# temaTSC.net
KiCad netlist of a schematic drawn in EAGLE
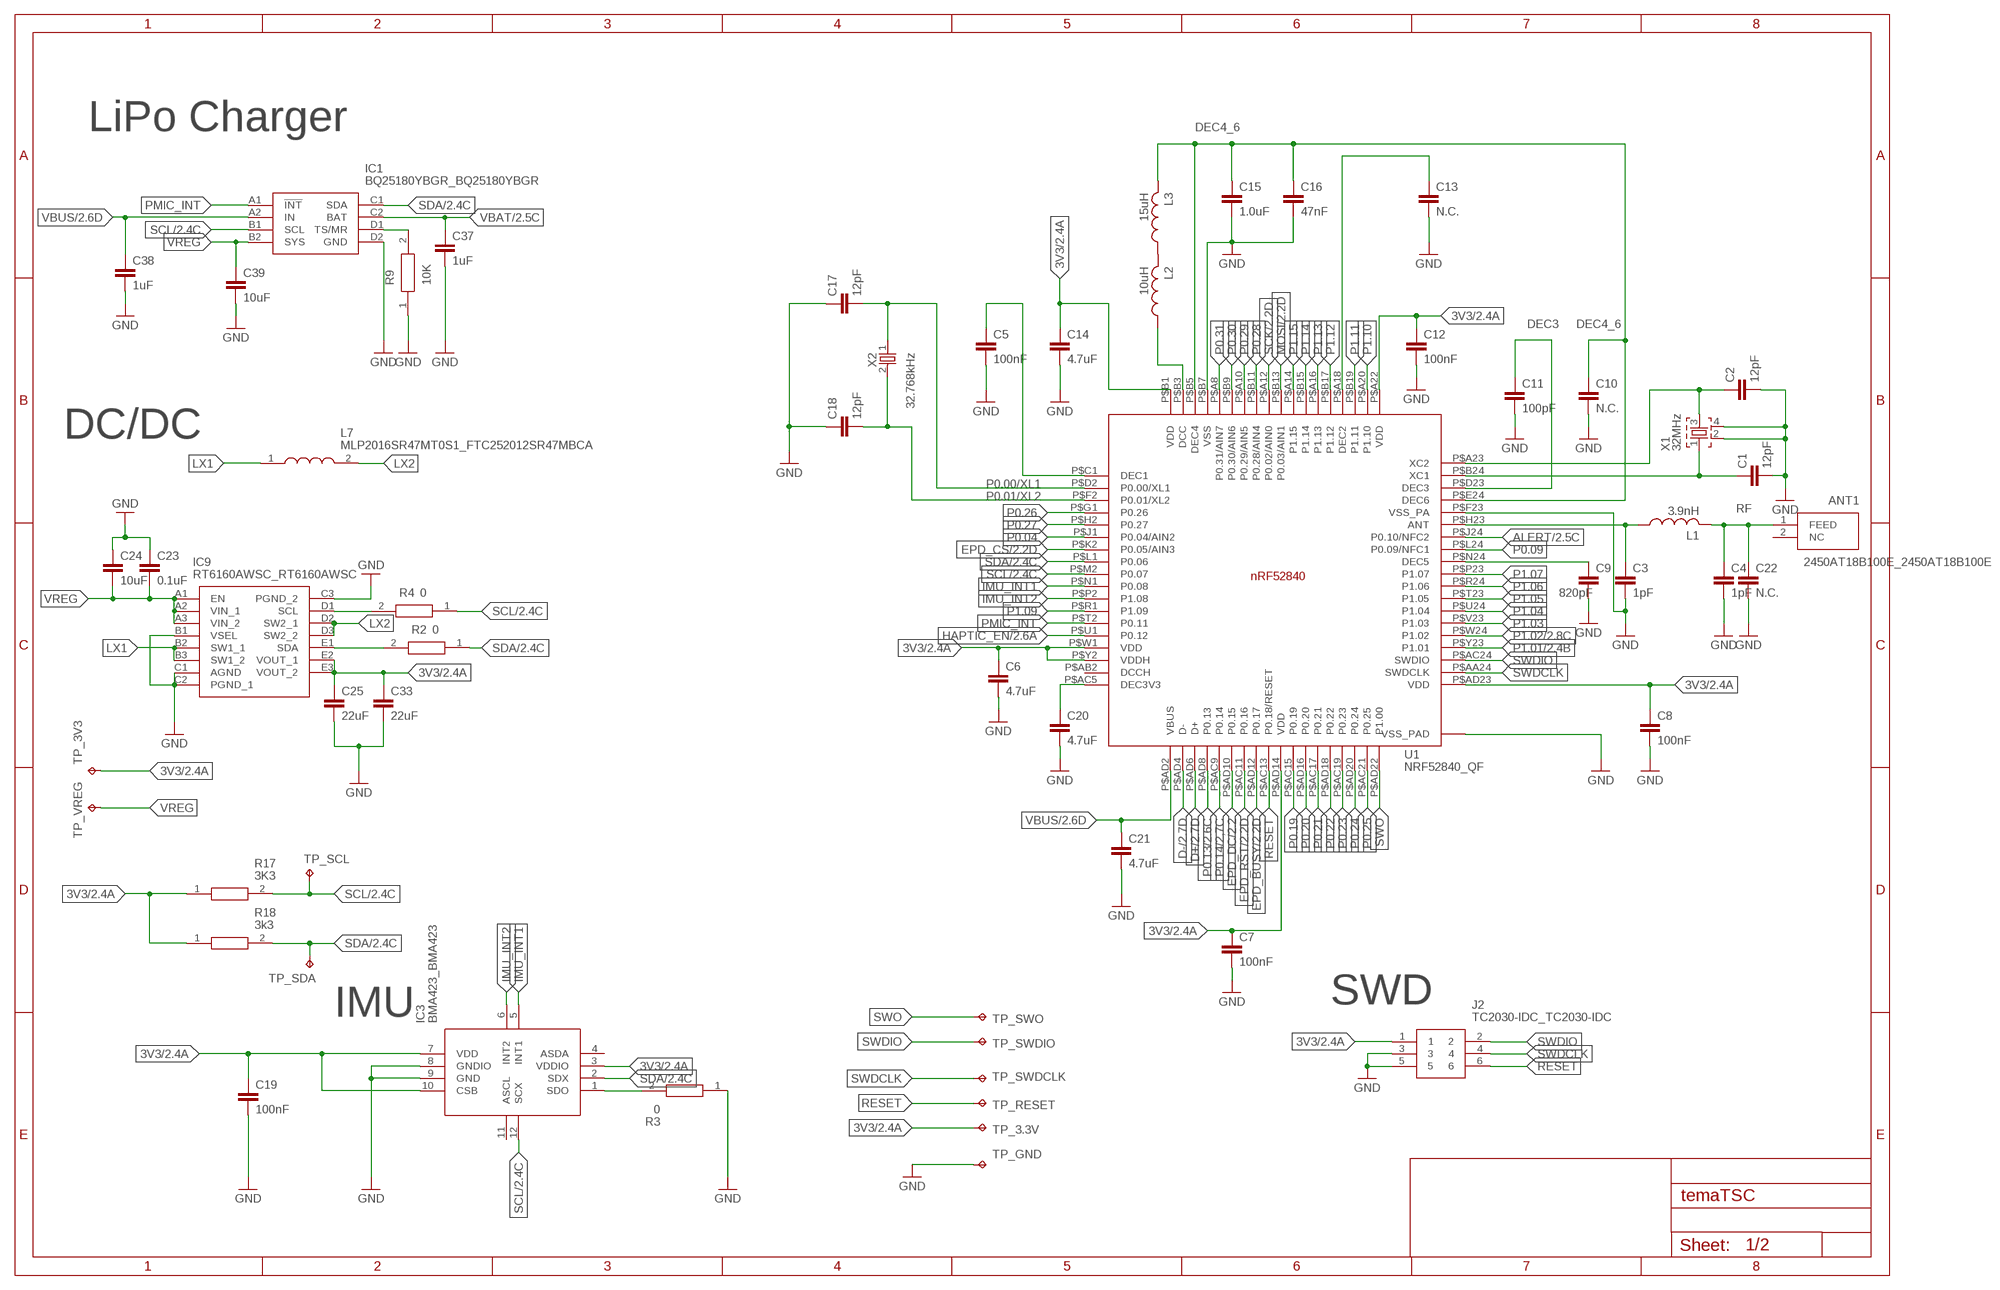
[diagram p0: schematic, sheet 1]
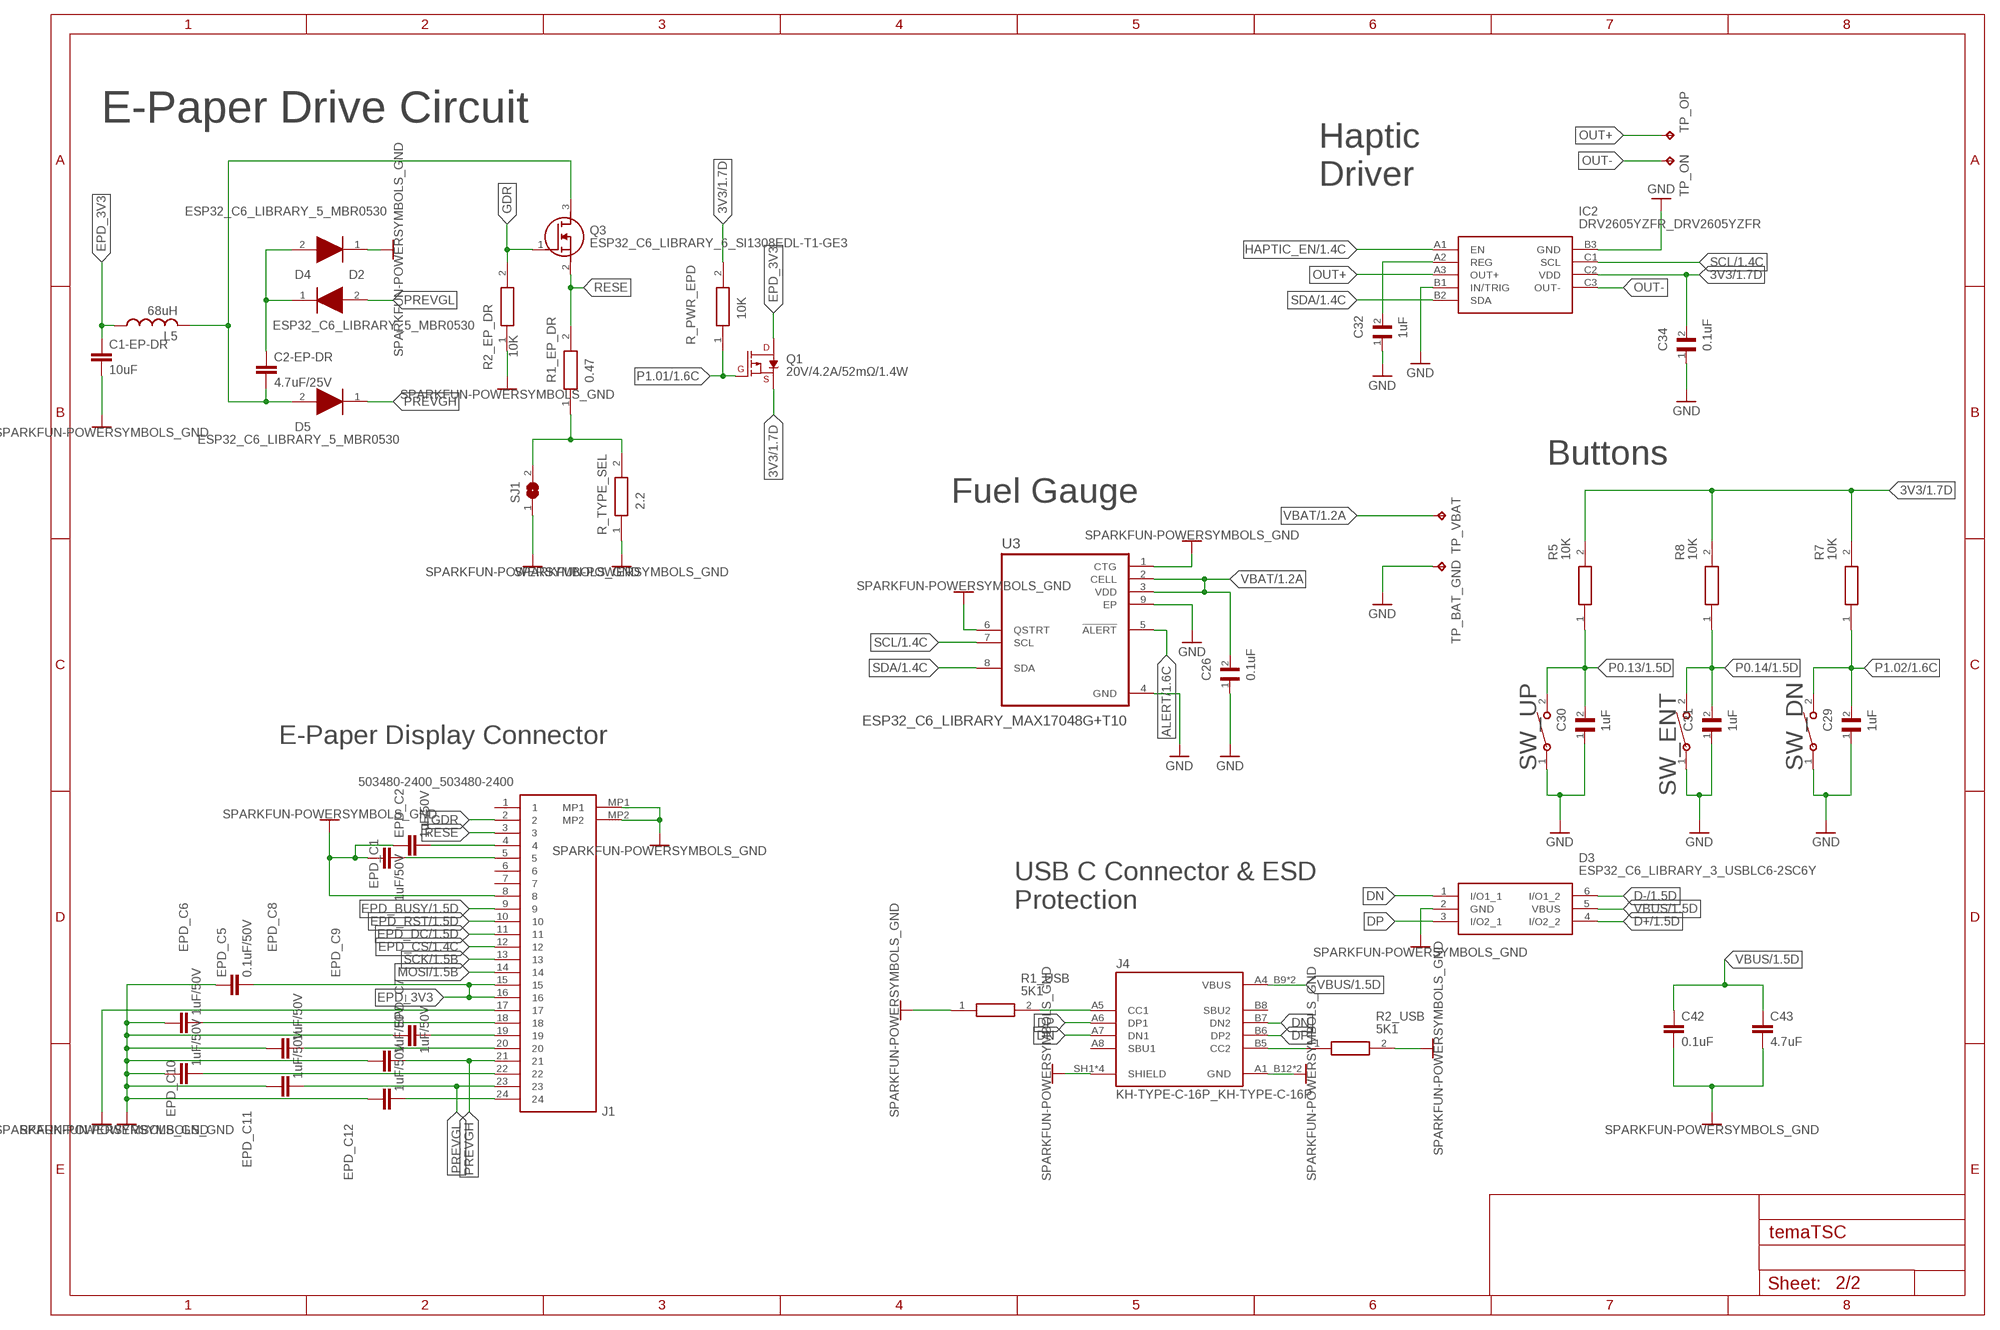
[diagram p1: schematic, sheet 2]

(export (version "E")
  (design (tool "Eeschema 10.0.6"))
  (components
    (comp (ref "ANT1")
      (value "2450AT18B100E_2450AT18B100E")
      (footprint "eagle-import:2450AT18B100E_ANTC3216X140N")
      (fields
        (field (name "ARROW_PART_NUMBER") "2450AT18B100E")
        (field (name "MOUSER_PART_NUMBER") "609-2450AT18B100E")
      )
      (libsource (lib "eagle-import") (part "2450AT18B100E_2450AT18B100E"))
    )
    (comp (ref "C1")
      (value "12pF")
      (footprint "eagle-import:NORDIC_NRF_3_RESC0201_L")
      (libsource (lib "eagle-import") (part "NORDIC_NRF_3_CAPACITOR_0201_L"))
    )
    (comp (ref "C2")
      (value "12pF")
      (footprint "eagle-import:NORDIC_NRF_3_RESC0201_L")
      (libsource (lib "eagle-import") (part "NORDIC_NRF_3_CAPACITOR_0201_L"))
    )
    (comp (ref "C3")
      (value "1pF")
      (footprint "eagle-import:NORDIC_NRF_3_RESC0201_L")
      (libsource (lib "eagle-import") (part "NORDIC_NRF_3_CAPACITOR_0201_L"))
    )
    (comp (ref "C4")
      (value "1pF")
      (footprint "eagle-import:NORDIC_NRF_3_RESC0201_L")
      (libsource (lib "eagle-import") (part "NORDIC_NRF_3_CAPACITOR_0201_L"))
    )
    (comp (ref "C5")
      (value "100nF")
      (footprint "eagle-import:NORDIC_NRF_3_RESC0201_L")
      (libsource (lib "eagle-import") (part "NORDIC_NRF_3_CAPACITOR_0201_L"))
    )
    (comp (ref "C6")
      (value "4.7uF")
      (footprint "eagle-import:NORDIC_NRF_3_RESC0402_L")
      (libsource (lib "eagle-import") (part "NORDIC_NRF_3_CAPACITOR_0402_L"))
    )
    (comp (ref "C7")
      (value "100nF")
      (footprint "eagle-import:NORDIC_NRF_3_RESC0201_L")
      (libsource (lib "eagle-import") (part "NORDIC_NRF_3_CAPACITOR_0201_L"))
    )
    (comp (ref "C8")
      (value "100nF")
      (footprint "eagle-import:NORDIC_NRF_3_RESC0201_L")
      (libsource (lib "eagle-import") (part "NORDIC_NRF_3_CAPACITOR_0201_L"))
    )
    (comp (ref "C9")
      (value "820pF")
      (footprint "eagle-import:NORDIC_NRF_3_RESC0201_L")
      (libsource (lib "eagle-import") (part "NORDIC_NRF_3_CAPACITOR_0201_L"))
    )
    (comp (ref "C10")
      (value "N.C.")
      (footprint "eagle-import:NORDIC_NRF_3_RESC0201_L")
      (libsource (lib "eagle-import") (part "NORDIC_NRF_3_CAPACITOR_0201_L"))
    )
    (comp (ref "C11")
      (value "100pF")
      (footprint "eagle-import:NORDIC_NRF_3_RESC0201_L")
      (libsource (lib "eagle-import") (part "NORDIC_NRF_3_CAPACITOR_0201_L"))
    )
    (comp (ref "C12")
      (value "100nF")
      (footprint "eagle-import:NORDIC_NRF_3_RESC0201_L")
      (libsource (lib "eagle-import") (part "NORDIC_NRF_3_CAPACITOR_0201_L"))
    )
    (comp (ref "C13")
      (value "N.C.")
      (footprint "eagle-import:NORDIC_NRF_3_RESC0201_L")
      (libsource (lib "eagle-import") (part "NORDIC_NRF_3_CAPACITOR_0201_L"))
    )
    (comp (ref "C14")
      (value "4.7uF")
      (footprint "eagle-import:NORDIC_NRF_3_RESC0402_L")
      (libsource (lib "eagle-import") (part "NORDIC_NRF_3_CAPACITOR_0402_L"))
    )
    (comp (ref "C15")
      (value "1.0uF")
      (footprint "eagle-import:NORDIC_NRF_3_RESC0402_L")
      (libsource (lib "eagle-import") (part "NORDIC_NRF_3_CAPACITOR_0402_L"))
    )
    (comp (ref "C16")
      (value "47nF")
      (footprint "eagle-import:NORDIC_NRF_3_RESC0201_L")
      (libsource (lib "eagle-import") (part "NORDIC_NRF_3_CAPACITOR_0201_L"))
    )
    (comp (ref "C17")
      (value "12pF")
      (footprint "eagle-import:NORDIC_NRF_3_RESC0201_L")
      (libsource (lib "eagle-import") (part "NORDIC_NRF_3_CAPACITOR_0201_L"))
    )
    (comp (ref "C18")
      (value "12pF")
      (footprint "eagle-import:NORDIC_NRF_3_RESC0201_L")
      (libsource (lib "eagle-import") (part "NORDIC_NRF_3_CAPACITOR_0201_L"))
    )
    (comp (ref "C19")
      (value "100nF")
      (footprint "eagle-import:NORDIC_NRF_3_RESC0201_L")
      (libsource (lib "eagle-import") (part "NORDIC_NRF_3_CAPACITOR_0201_L"))
    )
    (comp (ref "C20")
      (value "4.7uF")
      (footprint "eagle-import:NORDIC_NRF_3_RESC0402_L")
      (libsource (lib "eagle-import") (part "NORDIC_NRF_3_CAPACITOR_0402_L"))
    )
    (comp (ref "C21")
      (value "4.7uF")
      (footprint "eagle-import:NORDIC_NRF_3_RESC0402_L")
      (libsource (lib "eagle-import") (part "NORDIC_NRF_3_CAPACITOR_0402_L"))
    )
    (comp (ref "C22")
      (value "N.C.")
      (footprint "eagle-import:NORDIC_NRF_3_RESC0201_L")
      (libsource (lib "eagle-import") (part "NORDIC_NRF_3_CAPACITOR_0201_L"))
    )
    (comp (ref "C23")
      (value "0.1uF")
      (footprint "eagle-import:NORDIC_NRF_3_RESC0201_L")
      (libsource (lib "eagle-import") (part "NORDIC_NRF_3_CAPACITOR_0201_L"))
    )
    (comp (ref "C24")
      (value "10uF")
      (footprint "eagle-import:NORDIC_NRF_3_RESC0402_L")
      (libsource (lib "eagle-import") (part "NORDIC_NRF_3_CAPACITOR_0402_L"))
    )
    (comp (ref "C25")
      (value "22uF")
      (footprint "eagle-import:NORDIC_NRF_3_RESC0402_L")
      (libsource (lib "eagle-import") (part "NORDIC_NRF_3_CAPACITOR_0402_L"))
    )
    (comp (ref "C33")
      (value "22uF")
      (footprint "eagle-import:NORDIC_NRF_3_RESC0402_L")
      (libsource (lib "eagle-import") (part "NORDIC_NRF_3_CAPACITOR_0402_L"))
    )
    (comp (ref "C37")
      (value "1uF")
      (footprint "eagle-import:NORDIC_NRF_3_RESC0402_L")
      (libsource (lib "eagle-import") (part "NORDIC_NRF_3_CAPACITOR_0402_L"))
    )
    (comp (ref "C38")
      (value "1uF")
      (footprint "eagle-import:NORDIC_NRF_3_RESC0402_L")
      (libsource (lib "eagle-import") (part "NORDIC_NRF_3_CAPACITOR_0402_L"))
    )
    (comp (ref "C39")
      (value "10uF")
      (footprint "eagle-import:NORDIC_NRF_3_RESC0402_L")
      (libsource (lib "eagle-import") (part "NORDIC_NRF_3_CAPACITOR_0402_L"))
    )
    (comp (ref "IC1")
      (value "BQ25180YBGR_BQ25180YBGR")
      (footprint "eagle-import:BQ25180YBGR_BGA8C40P2X4_100X155X50")
      (fields
        (field (name "ARROW_PART_NUMBER") "BQ25180YBGR")
        (field (name "MOUSER_PART_NUMBER") "595-BQ25180YBGR")
      )
      (libsource (lib "eagle-import") (part "BQ25180YBGR_BQ25180YBGR"))
    )
    (comp (ref "IC3")
      (value "BMA423_BMA423")
      (footprint "eagle-import:BMA423_BMA423")
      (fields (field (name "ARROW_PART_NUMBER") "BMA423") (field (name "MOUSER_PART_NUMBER") "262-BMA423"))
      (libsource (lib "eagle-import") (part "BMA423_BMA423"))
    )
    (comp (ref "IC9")
      (value "RT6160AWSC_RT6160AWSC")
      (footprint "eagle-import:RT6160AWSC_BGA15C40P3X5_140X230X60")
      (fields
        (field (name "MANUFACTURER_PART_NUMBER") "RT6160AWSC")
        (field (name "MOUSER_PART_NUMBER") "835-RT6160AWSC")
      )
      (libsource (lib "eagle-import") (part "RT6160AWSC_RT6160AWSC"))
    )
    (comp (ref "J2")
      (value "TC2030-IDC_TC2030-IDC")
      (footprint "eagle-import:TC2030-IDC_TC2030IDC")
      (fields (field (name "MANUFACTURER_PART_NUMBER") "TC2030-IDC"))
      (libsource (lib "eagle-import") (part "TC2030-IDC_TC2030-IDC"))
    )
    (comp (ref "L1")
      (value "3.9nH")
      (footprint "eagle-import:NORDIC_NRF_2_RESC0402_L")
      (libsource (lib "eagle-import") (part "NORDIC_NRF_2_INDUCTOR_0402_L"))
    )
    (comp (ref "L2")
      (value "10uH")
      (footprint "eagle-import:NORDIC_NRF_2_RESC0402_L")
      (libsource (lib "eagle-import") (part "NORDIC_NRF_2_INDUCTOR_0402_L"))
    )
    (comp (ref "L3")
      (value "15uH")
      (footprint "eagle-import:NORDIC_NRF_2_RESC0402_L")
      (libsource (lib "eagle-import") (part "NORDIC_NRF_2_INDUCTOR_0402_L"))
    )
    (comp (ref "L7")
      (value "MLP2016SR47MT0S1_FTC252012SR47MBCA")
      (footprint "eagle-import:MLP2016SR47MT0S1_INDC2016X100N")
      (fields (field (name "MANUFACTURER_PART_NUMBER") "FTC252012SR47MBCA"))
      (libsource (lib "eagle-import") (part "MLP2016SR47MT0S1_FTC252012SR47MBCA"))
    )
    (comp (ref "R2")
      (value "0")
      (footprint "eagle-import:ERA-1AEB3401C_0201")
      (libsource (lib "eagle-import") (part "ERA-1AEB3401C_CPF0201D7K68C1"))
    )
    (comp (ref "R3")
      (value "0")
      (footprint "eagle-import:ERA-1AEB3401C_0201")
      (libsource (lib "eagle-import") (part "ERA-1AEB3401C_CPF0201D7K68C1"))
    )
    (comp (ref "R4")
      (value "0")
      (footprint "eagle-import:ERA-1AEB3401C_0201")
      (libsource (lib "eagle-import") (part "ERA-1AEB3401C_CPF0201D7K68C1"))
    )
    (comp (ref "R9")
      (value "10K")
      (footprint "eagle-import:ERA-1AEB3401C_0201")
      (libsource (lib "eagle-import") (part "ERA-1AEB3401C_CPF0201D7K68C1"))
    )
    (comp (ref "R17")
      (value "3K3")
      (footprint "eagle-import:ERA-1AEB3401C_0201")
      (libsource (lib "eagle-import") (part "ERA-1AEB3401C_CPF0201D7K68C1"))
    )
    (comp (ref "R18")
      (value "3k3")
      (footprint "eagle-import:ERA-1AEB3401C_0201")
      (libsource (lib "eagle-import") (part "ERA-1AEB3401C_CPF0201D7K68C1"))
    )
    (comp (ref "TP_3.3V")
      (value "HECTOR_WATCH_1_TPTP20R")
      (footprint "eagle-import:HECTOR_WATCH_1_TP20R")
      (libsource (lib "eagle-import") (part "HECTOR_WATCH_1_TPTP20R"))
    )
    (comp (ref "TP_3V3")
      (value "HECTOR_WATCH_1_TPTP20R")
      (footprint "eagle-import:HECTOR_WATCH_1_TP20R")
      (libsource (lib "eagle-import") (part "HECTOR_WATCH_1_TPTP20R"))
    )
    (comp (ref "TP_GND")
      (value "HECTOR_WATCH_1_TPTP20R")
      (footprint "eagle-import:HECTOR_WATCH_1_TP20R")
      (libsource (lib "eagle-import") (part "HECTOR_WATCH_1_TPTP20R"))
    )
    (comp (ref "TP_RESET")
      (value "HECTOR_WATCH_1_TPTP20R")
      (footprint "eagle-import:HECTOR_WATCH_1_TP20R")
      (libsource (lib "eagle-import") (part "HECTOR_WATCH_1_TPTP20R"))
    )
    (comp (ref "TP_SCL")
      (value "HECTOR_WATCH_1_TPTP20R")
      (footprint "eagle-import:HECTOR_WATCH_1_TP20R")
      (libsource (lib "eagle-import") (part "HECTOR_WATCH_1_TPTP20R"))
    )
    (comp (ref "TP_SDA")
      (value "HECTOR_WATCH_1_TPTP20R")
      (footprint "eagle-import:HECTOR_WATCH_1_TP20R")
      (libsource (lib "eagle-import") (part "HECTOR_WATCH_1_TPTP20R"))
    )
    (comp (ref "TP_SWDCLK")
      (value "HECTOR_WATCH_1_TPTP20R")
      (footprint "eagle-import:HECTOR_WATCH_1_TP20R")
      (libsource (lib "eagle-import") (part "HECTOR_WATCH_1_TPTP20R"))
    )
    (comp (ref "TP_SWDIO")
      (value "HECTOR_WATCH_1_TPTP20R")
      (footprint "eagle-import:HECTOR_WATCH_1_TP20R")
      (libsource (lib "eagle-import") (part "HECTOR_WATCH_1_TPTP20R"))
    )
    (comp (ref "TP_SWO")
      (value "HECTOR_WATCH_1_TPTP20R")
      (footprint "eagle-import:HECTOR_WATCH_1_TP20R")
      (libsource (lib "eagle-import") (part "HECTOR_WATCH_1_TPTP20R"))
    )
    (comp (ref "TP_VREG")
      (value "HECTOR_WATCH_1_TPTP20R")
      (footprint "eagle-import:HECTOR_WATCH_1_TP20R")
      (libsource (lib "eagle-import") (part "HECTOR_WATCH_1_TPTP20R"))
    )
    (comp (ref "U1")
      (value "NRF52840_QF")
      (footprint "eagle-import:NORDIC_NRF_4_AQFN50P700X700X85_HS-74N")
      (libsource (lib "eagle-import") (part "NORDIC_NRF_4_NRF52840_QF"))
    )
    (comp (ref "X1")
      (value "32MHz")
      (footprint "eagle-import:NORDIC_NRF_BT-XTAL_2016_N")
      (libsource (lib "eagle-import") (part "NORDIC_NRF_XTAL_32MHZ"))
    )
    (comp (ref "X2")
      (value "32.768kHz")
      (footprint "eagle-import:NORDIC_NRF_1_XTAL_3215_N")
      (libsource (lib "eagle-import") (part "NORDIC_NRF_1_XTAL_32KHZ"))
    )
    (comp (ref "C1-EP-DR")
      (value "10uF")
      (footprint "eagle-import:NORDIC_NRF_3_RESC0402_L")
      (libsource (lib "eagle-import") (part "NORDIC_NRF_3_CAPACITOR_0402_L"))
    )
    (comp (ref "C2-EP-DR")
      (value "4.7uF/25V")
      (footprint "eagle-import:NORDIC_NRF_3_RESC0402_L")
      (libsource (lib "eagle-import") (part "NORDIC_NRF_3_CAPACITOR_0402_L"))
    )
    (comp (ref "C26")
      (value "0.1uF")
      (footprint "eagle-import:GRM011R60J152KE01L_1_0201")
      (libsource (lib "eagle-import") (part "GRM011R60J152KE01L_1_GRM011R60J152KE01L"))
    )
    (comp (ref "C29")
      (value "1uF")
      (footprint "eagle-import:GRM011R60J152KE01L_1_0201")
      (libsource (lib "eagle-import") (part "GRM011R60J152KE01L_1_GRM011R60J152KE01L"))
    )
    (comp (ref "C30")
      (value "1uF")
      (footprint "eagle-import:GRM011R60J152KE01L_1_0201")
      (libsource (lib "eagle-import") (part "GRM011R60J152KE01L_1_GRM011R60J152KE01L"))
    )
    (comp (ref "C31")
      (value "1uF")
      (footprint "eagle-import:GRM011R60J152KE01L_1_0201")
      (libsource (lib "eagle-import") (part "GRM011R60J152KE01L_1_GRM011R60J152KE01L"))
    )
    (comp (ref "C32")
      (value "1uF")
      (footprint "eagle-import:GRM011R60J152KE01L_1_0201")
      (libsource (lib "eagle-import") (part "GRM011R60J152KE01L_1_GRM011R60J152KE01L"))
    )
    (comp (ref "C34")
      (value "0.1uF")
      (footprint "eagle-import:GRM011R60J152KE01L_1_0201")
      (libsource (lib "eagle-import") (part "GRM011R60J152KE01L_1_GRM011R60J152KE01L"))
    )
    (comp (ref "C42")
      (value "0.1uF")
      (footprint "eagle-import:NORDIC_NRF_3_RESC0201_L")
      (libsource (lib "eagle-import") (part "NORDIC_NRF_3_CAPACITOR_0201_L"))
    )
    (comp (ref "C43")
      (value "4.7uF")
      (footprint "eagle-import:NORDIC_NRF_3_RESC0402_L")
      (libsource (lib "eagle-import") (part "NORDIC_NRF_3_CAPACITOR_0402_L"))
    )
    (comp (ref "D2")
      (value "ESP32_C6_LIBRARY_5_MBR0530")
      (footprint "eagle-import:ESP32_C6_LIBRARY_5_SOD3716X135N")
      (fields (field (name "MF") "ON Semiconductor") (field (name "MP") "MBR0530"))
      (libsource (lib "eagle-import") (part "ESP32_C6_LIBRARY_5_MBR0530"))
    )
    (comp (ref "D3")
      (value "ESP32_C6_LIBRARY_3_USBLC6-2SC6Y")
      (footprint "eagle-import:ESP32_C6_LIBRARY_3_SOT95P280X145-6N")
      (fields (field (name "MF") "STMicroelectronics") (field (name "MP") "USBLC6-2SC6Y"))
      (libsource (lib "eagle-import") (part "ESP32_C6_LIBRARY_3_USBLC6-2SC6Y"))
    )
    (comp (ref "D4")
      (value "ESP32_C6_LIBRARY_5_MBR0530")
      (footprint "eagle-import:ESP32_C6_LIBRARY_5_SOD3716X135N")
      (fields (field (name "MF") "ON Semiconductor") (field (name "MP") "MBR0530"))
      (libsource (lib "eagle-import") (part "ESP32_C6_LIBRARY_5_MBR0530"))
    )
    (comp (ref "D5")
      (value "ESP32_C6_LIBRARY_5_MBR0530")
      (footprint "eagle-import:ESP32_C6_LIBRARY_5_SOD3716X135N")
      (fields (field (name "MF") "ON Semiconductor") (field (name "MP") "MBR0530"))
      (libsource (lib "eagle-import") (part "ESP32_C6_LIBRARY_5_MBR0530"))
    )
    (comp (ref "EPD_C1")
      (value "1uF/50V")
      (footprint "eagle-import:NORDIC_NRF_3_RESC0402_L")
      (libsource (lib "eagle-import") (part "NORDIC_NRF_3_CAPACITOR_0402_L"))
    )
    (comp (ref "EPD_C2")
      (value "1uF/50V")
      (footprint "eagle-import:NORDIC_NRF_3_RESC0402_L")
      (libsource (lib "eagle-import") (part "NORDIC_NRF_3_CAPACITOR_0402_L"))
    )
    (comp (ref "EPD_C5")
      (value "0.1uF/50V")
      (footprint "eagle-import:NORDIC_NRF_3_RESC0201_L")
      (libsource (lib "eagle-import") (part "NORDIC_NRF_3_CAPACITOR_0201_L"))
    )
    (comp (ref "EPD_C6")
      (value "1uF/50V")
      (footprint "eagle-import:NORDIC_NRF_3_RESC0402_L")
      (libsource (lib "eagle-import") (part "NORDIC_NRF_3_CAPACITOR_0402_L"))
    )
    (comp (ref "EPD_C7")
      (value "1uF/50V")
      (footprint "eagle-import:NORDIC_NRF_3_RESC0402_L")
      (libsource (lib "eagle-import") (part "NORDIC_NRF_3_CAPACITOR_0402_L"))
    )
    (comp (ref "EPD_C8")
      (value "1uF/50V")
      (footprint "eagle-import:NORDIC_NRF_3_RESC0402_L")
      (libsource (lib "eagle-import") (part "NORDIC_NRF_3_CAPACITOR_0402_L"))
    )
    (comp (ref "EPD_C9")
      (value "1uF/50V")
      (footprint "eagle-import:NORDIC_NRF_3_RESC0402_L")
      (libsource (lib "eagle-import") (part "NORDIC_NRF_3_CAPACITOR_0402_L"))
    )
    (comp (ref "EPD_C10")
      (value "1uF/50V")
      (footprint "eagle-import:NORDIC_NRF_3_RESC0402_L")
      (libsource (lib "eagle-import") (part "NORDIC_NRF_3_CAPACITOR_0402_L"))
    )
    (comp (ref "EPD_C11")
      (value "1uF/50V")
      (footprint "eagle-import:NORDIC_NRF_3_RESC0402_L")
      (libsource (lib "eagle-import") (part "NORDIC_NRF_3_CAPACITOR_0402_L"))
    )
    (comp (ref "EPD_C12")
      (value "1uF/50V")
      (footprint "eagle-import:NORDIC_NRF_3_RESC0402_L")
      (libsource (lib "eagle-import") (part "NORDIC_NRF_3_CAPACITOR_0402_L"))
    )
    (comp (ref "IC2")
      (value "DRV2605YZFR_DRV2605YZFR")
      (footprint "eagle-import:DRV2605YZFR_BGA9C50P3X3_144X144X62")
      (fields (field (name "ARROW_PART_NUMBER") "DRV2605YZFR"))
      (libsource (lib "eagle-import") (part "DRV2605YZFR_DRV2605YZFR"))
    )
    (comp (ref "J1")
      (value "503480-2400_503480-2400")
      (footprint "eagle-import:503480-2400_5034802400")
      (fields
        (field (name "MANUFACTURER_PART_NUMBER") "503480-2400")
        (field (name "MOUSER_PART_NUMBER") "538-503480-2400")
      )
      (libsource (lib "eagle-import") (part "503480-2400_503480-2400"))
    )
    (comp (ref "J4")
      (value "KH-TYPE-C-16P_KH-TYPE-C-16P")
      (footprint "eagle-import:KH-TYPE-C-16P_KINGHELM_KH-TYPE-C-16P")
      (fields (field (name "MF") "kinghelm") (field (name "MP") "KH-TYPE-C-16P"))
      (libsource (lib "eagle-import") (part "KH-TYPE-C-16P_KH-TYPE-C-16P"))
    )
    (comp (ref "L5")
      (value "68uH")
      (footprint "eagle-import:NORDIC_NRF_2_RESC0402_L")
      (libsource (lib "eagle-import") (part "NORDIC_NRF_2_INDUCTOR_0402_L"))
    )
    (comp (ref "Q1")
      (value "20V/4.2A/52mΩ/1.4W")
      (footprint "eagle-import:ESP32_C6_LIBRARY_4_ESP32_C6_LIBRARY_4_ESP32_C6_LIBRARY_4_ESP32_C6_LIBRARY_4_ESP32_WROVER_SPARKFUN-DISCRETESEMI_SOT23-3")
      (libsource (lib "eagle-import") (part "ESP32_C6_LIBRARY_4_ESP32_WROVER_SPARKFUN-DISCRETESEMI_MOSFET_PCH-DMG2305UX-7"))
    )
    (comp (ref "Q3")
      (value "ESP32_C6_LIBRARY_6_SI1308EDL-T1-GE3")
      (footprint "eagle-import:ESP32_C6_LIBRARY_6_SOT65P210X110-3N")
      (fields (field (name "MF") "Vishay Siliconix") (field (name "MP") "SI1308EDL-T1-GE3"))
      (libsource (lib "eagle-import") (part "ESP32_C6_LIBRARY_6_SI1308EDL-T1-GE3"))
    )
    (comp (ref "R1_EP_DR")
      (value "0.47")
      (footprint "eagle-import:ERA-1AEB3401C_0201")
      (libsource (lib "eagle-import") (part "ERA-1AEB3401C_CPF0201D7K68C1"))
    )
    (comp (ref "R1_USB")
      (value "5K1")
      (footprint "eagle-import:ERA-1AEB3401C_0201")
      (libsource (lib "eagle-import") (part "ERA-1AEB3401C_CPF0201D7K68C1"))
    )
    (comp (ref "R2_EP_DR")
      (value "10K")
      (footprint "eagle-import:ERA-1AEB3401C_0201")
      (libsource (lib "eagle-import") (part "ERA-1AEB3401C_CPF0201D7K68C1"))
    )
    (comp (ref "R2_USB")
      (value "5K1")
      (footprint "eagle-import:ERA-1AEB3401C_0201")
      (libsource (lib "eagle-import") (part "ERA-1AEB3401C_CPF0201D7K68C1"))
    )
    (comp (ref "R5")
      (value "10K")
      (footprint "eagle-import:ERA-1AEB3401C_0201")
      (libsource (lib "eagle-import") (part "ERA-1AEB3401C_CPF0201D7K68C1"))
    )
    (comp (ref "R7")
      (value "10K")
      (footprint "eagle-import:ERA-1AEB3401C_0201")
      (libsource (lib "eagle-import") (part "ERA-1AEB3401C_CPF0201D7K68C1"))
    )
    (comp (ref "R8")
      (value "10K")
      (footprint "eagle-import:ERA-1AEB3401C_0201")
      (libsource (lib "eagle-import") (part "ERA-1AEB3401C_CPF0201D7K68C1"))
    )
    (comp (ref "R_PWR_EPD")
      (value "10K")
      (footprint "eagle-import:ERA-1AEB3401C_0201")
      (libsource (lib "eagle-import") (part "ERA-1AEB3401C_CPF0201D7K68C1"))
    )
    (comp (ref "R_TYPE_SEL")
      (value "2.2")
      (footprint "eagle-import:ERA-1AEB3401C_0201")
      (libsource (lib "eagle-import") (part "ERA-1AEB3401C_CPF0201D7K68C1"))
    )
    (comp (ref "SJ1")
      (value "ESP32_C6_LIBRARY_7_JUMPER_SJ")
      (footprint "eagle-import:ESP32_C6_LIBRARY_7_JUMPER_SJ")
      (libsource (lib "eagle-import") (part "ESP32_C6_LIBRARY_7_JUMPER_SJ"))
    )
    (comp (ref "SW_DN")
      (value "2025-10-22_07-23-44_LIBRARY_EVP-AKE31ASW_EVP-AKE31A_PAN")
      (footprint "eagle-import:2025-10-22_07-23-44_LIBRARY_SW_EVP-AKE31A_PAN")
      (fields
        (field (name "MANUFACTURER_PART_NUMBER") "EVP-AKE31A")
        (field (name "COPYRIGHT") "Copyright (C) 2025 Ultra Librarian. All rights reserved.")
      )
      (libsource (lib "eagle-import") (part "2025-10-22_07-23-44_LIBRARY_EVP-AKE31ASW_EVP-AKE31A_PAN"))
    )
    (comp (ref "SW_ENT")
      (value "2025-10-22_07-23-44_LIBRARY_EVP-AKE31ASW_EVP-AKE31A_PAN")
      (footprint "eagle-import:2025-10-22_07-23-44_LIBRARY_SW_EVP-AKE31A_PAN")
      (fields
        (field (name "MANUFACTURER_PART_NUMBER") "EVP-AKE31A")
        (field (name "COPYRIGHT") "Copyright (C) 2025 Ultra Librarian. All rights reserved.")
      )
      (libsource (lib "eagle-import") (part "2025-10-22_07-23-44_LIBRARY_EVP-AKE31ASW_EVP-AKE31A_PAN"))
    )
    (comp (ref "SW_UP")
      (value "2025-10-22_07-23-44_LIBRARY_EVP-AKE31ASW_EVP-AKE31A_PAN")
      (footprint "eagle-import:2025-10-22_07-23-44_LIBRARY_SW_EVP-AKE31A_PAN")
      (fields
        (field (name "MANUFACTURER_PART_NUMBER") "EVP-AKE31A")
        (field (name "COPYRIGHT") "Copyright (C) 2025 Ultra Librarian. All rights reserved.")
      )
      (libsource (lib "eagle-import") (part "2025-10-22_07-23-44_LIBRARY_EVP-AKE31ASW_EVP-AKE31A_PAN"))
    )
    (comp (ref "TP_BAT_GND")
      (value "HECTOR_WATCH_1_TPTP20R")
      (footprint "eagle-import:HECTOR_WATCH_1_TP20R")
      (libsource (lib "eagle-import") (part "HECTOR_WATCH_1_TPTP20R"))
    )
    (comp (ref "TP_ON")
      (value "HECTOR_WATCH_1_TPTP20R")
      (footprint "eagle-import:HECTOR_WATCH_1_TP20R")
      (libsource (lib "eagle-import") (part "HECTOR_WATCH_1_TPTP20R"))
    )
    (comp (ref "TP_OP")
      (value "HECTOR_WATCH_1_TPTP20R")
      (footprint "eagle-import:HECTOR_WATCH_1_TP20R")
      (libsource (lib "eagle-import") (part "HECTOR_WATCH_1_TPTP20R"))
    )
    (comp (ref "TP_VBAT")
      (value "HECTOR_WATCH_1_TPTP20R")
      (footprint "eagle-import:HECTOR_WATCH_1_TP20R")
      (libsource (lib "eagle-import") (part "HECTOR_WATCH_1_TPTP20R"))
    )
    (comp (ref "U3")
      (value "ESP32_C6_LIBRARY_MAX17048G+T10")
      (footprint "eagle-import:ESP32_C6_LIBRARY_SON50P200X200X80-9N")
      (fields (field (name "MF") "Analog Devices") (field (name "MP") "MAX17048G+T10"))
      (libsource (lib "eagle-import") (part "ESP32_C6_LIBRARY_MAX17048G+T10"))
    )
  )
  (nets
    (net (code "1") (name "3V3{slash}1.7D") (class "Default")
      (node (ref "C34") (pin "2") (pinfunction "2_2") (pintype "passive"))
      (node (ref "IC2") (pin "C2") (pinfunction "VDD_C2") (pintype "bidirectional"))
      (node (ref "Q1") (pin "2") (pinfunction "S_2") (pintype "bidirectional"))
      (node (ref "R5") (pin "2") (pinfunction "2_2") (pintype "bidirectional"))
      (node (ref "R7") (pin "2") (pinfunction "2_2") (pintype "bidirectional"))
      (node (ref "R8") (pin "2") (pinfunction "2_2") (pintype "bidirectional"))
      (node (ref "R_PWR_EPD") (pin "2") (pinfunction "2_2") (pintype "bidirectional"))
    )
    (net (code "2") (name "3V3{slash}2.4A") (class "Default")
      (node (ref "C12") (pin "1") (pinfunction "1_1") (pintype "passive"))
      (node (ref "C14") (pin "1") (pinfunction "1_1") (pintype "passive"))
      (node (ref "C19") (pin "1") (pinfunction "1_1") (pintype "passive"))
      (node (ref "C25") (pin "1") (pinfunction "1_1") (pintype "passive"))
      (node (ref "C33") (pin "1") (pinfunction "1_1") (pintype "passive"))
      (node (ref "C6") (pin "1") (pinfunction "1_1") (pintype "passive"))
      (node (ref "C7") (pin "1") (pinfunction "1_1") (pintype "passive"))
      (node (ref "C8") (pin "1") (pinfunction "1_1") (pintype "passive"))
      (node (ref "IC3") (pin "10") (pinfunction "CSB_10") (pintype "bidirectional"))
      (node (ref "IC3") (pin "3") (pinfunction "VDDIO_3") (pintype "bidirectional"))
      (node (ref "IC3") (pin "7") (pinfunction "VDD_7") (pintype "bidirectional"))
      (node (ref "IC9") (pin "E2") (pinfunction "VOUT_1_E2") (pintype "bidirectional"))
      (node (ref "IC9") (pin "E3") (pinfunction "VOUT_2_E3") (pintype "bidirectional"))
      (node (ref "J2") (pin "1") (pinfunction "1_1") (pintype "bidirectional"))
      (node (ref "R17") (pin "1") (pinfunction "1_1") (pintype "bidirectional"))
      (node (ref "R18") (pin "1") (pinfunction "1_1") (pintype "bidirectional"))
      (node (ref "TP_3.3V") (pin "TP") (pinfunction "TP_TP") (pintype "input"))
      (node (ref "TP_3V3") (pin "TP") (pinfunction "TP_TP") (pintype "input"))
      (node (ref "U1") (pin "P$A22") (pinfunction "VDD_P$A22") (pintype "power_in"))
      (node (ref "U1") (pin "P$AD14") (pinfunction "VDD_P$AD14") (pintype "power_in"))
      (node (ref "U1") (pin "P$AD23") (pinfunction "VDD_P$AD23") (pintype "power_in"))
      (node (ref "U1") (pin "P$B1") (pinfunction "VDD_P$B1") (pintype "power_in"))
      (node (ref "U1") (pin "P$W1") (pinfunction "VDD_P$W1") (pintype "power_in"))
      (node (ref "U1") (pin "P$Y2") (pinfunction "VDDH_P$Y2") (pintype "power_in"))
    )
    (net (code "3") (name "ALERT{slash}1.6C") (class "Default")
      (node (ref "U3") (pin "5") (pinfunction "~{ALERT}_5") (pintype "output"))
    )
    (net (code "4") (name "ALERT{slash}2.5C") (class "Default")
      (node (ref "U1") (pin "P$J24") (pinfunction "P0.10/NFC2_P$J24") (pintype "bidirectional"))
    )
    (net (code "5") (name "D+{slash}1.5D") (class "Default")
      (node (ref "D3") (pin "4") (pinfunction "I/O2_2_4") (pintype "bidirectional"))
    )
    (net (code "6") (name "D+{slash}2.7D") (class "Default")
      (node (ref "U1") (pin "P$AD6") (pinfunction "D+_P$AD6") (pintype "bidirectional"))
    )
    (net (code "7") (name "D-{slash}1.5D") (class "Default")
      (node (ref "D3") (pin "6") (pinfunction "I/O1_2_6") (pintype "bidirectional"))
    )
    (net (code "8") (name "D-{slash}2.7D") (class "Default")
      (node (ref "U1") (pin "P$AD4") (pinfunction "D-_P$AD4") (pintype "bidirectional"))
    )
    (net (code "9") (name "DEC3") (class "Default")
      (node (ref "C11") (pin "1") (pinfunction "1_1") (pintype "passive"))
      (node (ref "U1") (pin "P$D23") (pinfunction "DEC3_P$D23") (pintype "bidirectional"))
    )
    (net (code "10") (name "DEC4_6") (class "Default")
      (node (ref "C10") (pin "1") (pinfunction "1_1") (pintype "passive"))
      (node (ref "C15") (pin "1") (pinfunction "1_1") (pintype "passive"))
      (node (ref "C16") (pin "1") (pinfunction "1_1") (pintype "passive"))
      (node (ref "L3") (pin "2") (pinfunction "2_2") (pintype "passive"))
      (node (ref "U1") (pin "P$B5") (pinfunction "DEC4_P$B5") (pintype "power_in"))
      (node (ref "U1") (pin "P$E24") (pinfunction "DEC6_P$E24") (pintype "bidirectional"))
    )
    (net (code "11") (name "DN") (class "Default")
      (node (ref "D3") (pin "1") (pinfunction "I/O1_1_1") (pintype "bidirectional"))
      (node (ref "J4") (pin "A7") (pinfunction "DN1_A7") (pintype "bidirectional"))
      (node (ref "J4") (pin "B7") (pinfunction "DN2_B7") (pintype "bidirectional"))
    )
    (net (code "12") (name "DP") (class "Default")
      (node (ref "D3") (pin "3") (pinfunction "I/O2_1_3") (pintype "bidirectional"))
      (node (ref "J4") (pin "A6") (pinfunction "DP1_A6") (pintype "bidirectional"))
      (node (ref "J4") (pin "B6") (pinfunction "DP2_B6") (pintype "bidirectional"))
    )
    (net (code "13") (name "EPD_3V3") (class "Default")
      (node (ref "C1-EP-DR") (pin "1") (pinfunction "1_1") (pintype "passive"))
      (node (ref "EPD_C5") (pin "2") (pinfunction "2_2") (pintype "passive"))
      (node (ref "J1") (pin "15") (pinfunction "15_15") (pintype "bidirectional"))
      (node (ref "J1") (pin "16") (pinfunction "16_16") (pintype "bidirectional"))
      (node (ref "L5") (pin "1") (pinfunction "1_1") (pintype "passive"))
      (node (ref "Q1") (pin "3") (pinfunction "D_3") (pintype "bidirectional"))
    )
    (net (code "14") (name "EPD_BUSY{slash}1.5D") (class "Default")
      (node (ref "J1") (pin "9") (pinfunction "9_9") (pintype "bidirectional"))
    )
    (net (code "15") (name "EPD_BUSY{slash}2.2D") (class "Default")
      (node (ref "U1") (pin "P$AD12") (pinfunction "P0.17_P$AD12") (pintype "bidirectional"))
    )
    (net (code "16") (name "EPD_CS{slash}1.4C") (class "Default")
      (node (ref "J1") (pin "12") (pinfunction "12_12") (pintype "bidirectional"))
    )
    (net (code "17") (name "EPD_CS{slash}2.2D") (class "Default")
      (node (ref "U1") (pin "P$K2") (pinfunction "P0.05/AIN3_P$K2") (pintype "bidirectional"))
    )
    (net (code "18") (name "EPD_DC{slash}1.5D") (class "Default")
      (node (ref "J1") (pin "11") (pinfunction "11_11") (pintype "bidirectional"))
    )
    (net (code "19") (name "EPD_DC{slash}2.2") (class "Default")
      (node (ref "U1") (pin "P$AD10") (pinfunction "P0.15_P$AD10") (pintype "bidirectional"))
    )
    (net (code "20") (name "EPD_RST{slash}1.5D") (class "Default")
      (node (ref "J1") (pin "10") (pinfunction "10_10") (pintype "bidirectional"))
    )
    (net (code "21") (name "EPD_RST{slash}2.2D") (class "Default")
      (node (ref "U1") (pin "P$AC11") (pinfunction "P0.16_P$AC11") (pintype "bidirectional"))
    )
    (net (code "22") (name "GDR") (class "Default")
      (node (ref "J1") (pin "2") (pinfunction "2_2") (pintype "bidirectional"))
      (node (ref "Q3") (pin "1") (pinfunction "G_1") (pintype "bidirectional"))
      (node (ref "R2_EP_DR") (pin "2") (pinfunction "2_2") (pintype "bidirectional"))
    )
    (net (code "23") (name "GND") (class "Default")
      (node (ref "C1") (pin "2") (pinfunction "2_2") (pintype "passive"))
      (node (ref "C1-EP-DR") (pin "2") (pinfunction "2_2") (pintype "passive"))
      (node (ref "C10") (pin "2") (pinfunction "2_2") (pintype "passive"))
      (node (ref "C11") (pin "2") (pinfunction "2_2") (pintype "passive"))
      (node (ref "C12") (pin "2") (pinfunction "2_2") (pintype "passive"))
      (node (ref "C13") (pin "2") (pinfunction "2_2") (pintype "passive"))
      (node (ref "C14") (pin "2") (pinfunction "2_2") (pintype "passive"))
      (node (ref "C15") (pin "2") (pinfunction "2_2") (pintype "passive"))
      (node (ref "C16") (pin "2") (pinfunction "2_2") (pintype "passive"))
      (node (ref "C17") (pin "1") (pinfunction "1_1") (pintype "passive"))
      (node (ref "C18") (pin "1") (pinfunction "1_1") (pintype "passive"))
      (node (ref "C19") (pin "2") (pinfunction "2_2") (pintype "passive"))
      (node (ref "C2") (pin "2") (pinfunction "2_2") (pintype "passive"))
      (node (ref "C20") (pin "2") (pinfunction "2_2") (pintype "passive"))
      (node (ref "C21") (pin "2") (pinfunction "2_2") (pintype "passive"))
      (node (ref "C22") (pin "2") (pinfunction "2_2") (pintype "passive"))
      (node (ref "C23") (pin "1") (pinfunction "1_1") (pintype "passive"))
      (node (ref "C24") (pin "1") (pinfunction "1_1") (pintype "passive"))
      (node (ref "C25") (pin "2") (pinfunction "2_2") (pintype "passive"))
      (node (ref "C26") (pin "1") (pinfunction "1_1") (pintype "passive"))
      (node (ref "C29") (pin "1") (pinfunction "1_1") (pintype "passive"))
      (node (ref "C3") (pin "2") (pinfunction "2_2") (pintype "passive"))
      (node (ref "C30") (pin "1") (pinfunction "1_1") (pintype "passive"))
      (node (ref "C31") (pin "1") (pinfunction "1_1") (pintype "passive"))
      (node (ref "C32") (pin "1") (pinfunction "1_1") (pintype "passive"))
      (node (ref "C33") (pin "2") (pinfunction "2_2") (pintype "passive"))
      (node (ref "C34") (pin "1") (pinfunction "1_1") (pintype "passive"))
      (node (ref "C37") (pin "2") (pinfunction "2_2") (pintype "passive"))
      (node (ref "C38") (pin "2") (pinfunction "2_2") (pintype "passive"))
      (node (ref "C39") (pin "2") (pinfunction "2_2") (pintype "passive"))
      (node (ref "C4") (pin "2") (pinfunction "2_2") (pintype "passive"))
      (node (ref "C42") (pin "2") (pinfunction "2_2") (pintype "passive"))
      (node (ref "C43") (pin "2") (pinfunction "2_2") (pintype "passive"))
      (node (ref "C5") (pin "2") (pinfunction "2_2") (pintype "passive"))
      (node (ref "C6") (pin "2") (pinfunction "2_2") (pintype "passive"))
      (node (ref "C7") (pin "2") (pinfunction "2_2") (pintype "passive"))
      (node (ref "C8") (pin "2") (pinfunction "2_2") (pintype "passive"))
      (node (ref "C9") (pin "2") (pinfunction "2_2") (pintype "passive"))
      (node (ref "D3") (pin "2") (pinfunction "GND_2") (pintype "bidirectional"))
      (node (ref "D4") (pin "1") (pinfunction "K_1") (pintype "bidirectional"))
      (node (ref "EPD_C1") (pin "1") (pinfunction "1_1") (pintype "passive"))
      (node (ref "EPD_C10") (pin "1") (pinfunction "1_1") (pintype "passive"))
      (node (ref "EPD_C11") (pin "1") (pinfunction "1_1") (pintype "passive"))
      (node (ref "EPD_C12") (pin "1") (pinfunction "1_1") (pintype "passive"))
      (node (ref "EPD_C2") (pin "1") (pinfunction "1_1") (pintype "passive"))
      (node (ref "EPD_C5") (pin "1") (pinfunction "1_1") (pintype "passive"))
      (node (ref "EPD_C6") (pin "1") (pinfunction "1_1") (pintype "passive"))
      (node (ref "EPD_C7") (pin "1") (pinfunction "1_1") (pintype "passive"))
      (node (ref "EPD_C8") (pin "1") (pinfunction "1_1") (pintype "passive"))
      (node (ref "EPD_C9") (pin "1") (pinfunction "1_1") (pintype "passive"))
      (node (ref "IC1") (pin "D2") (pinfunction "GND_D2") (pintype "bidirectional"))
      (node (ref "IC2") (pin "B1") (pinfunction "IN/TRIG_B1") (pintype "bidirectional"))
      (node (ref "IC2") (pin "B3") (pinfunction "GND_B3") (pintype "bidirectional"))
      (node (ref "IC3") (pin "8") (pinfunction "GNDIO_8") (pintype "bidirectional"))
      (node (ref "IC3") (pin "9") (pinfunction "GND_9") (pintype "bidirectional"))
      (node (ref "IC9") (pin "B1") (pinfunction "VSEL_B1") (pintype "bidirectional"))
      (node (ref "IC9") (pin "C1") (pinfunction "AGND_C1") (pintype "bidirectional"))
      (node (ref "IC9") (pin "C2") (pinfunction "PGND_1_C2") (pintype "bidirectional"))
      (node (ref "IC9") (pin "C3") (pinfunction "PGND_2_C3") (pintype "bidirectional"))
      (node (ref "J1") (pin "17") (pinfunction "17_17") (pintype "bidirectional"))
      (node (ref "J1") (pin "8") (pinfunction "8_8") (pintype "bidirectional"))
      (node (ref "J1") (pin "MP1") (pinfunction "MP1_MP1") (pintype "bidirectional"))
      (node (ref "J1") (pin "MP2") (pinfunction "MP2_MP2") (pintype "bidirectional"))
      (node (ref "J2") (pin "3") (pinfunction "3_3") (pintype "bidirectional"))
      (node (ref "J2") (pin "5") (pinfunction "5_5") (pintype "bidirectional"))
      (node (ref "J4") (pin "A12_B1") (pinfunction "GND_A12_B1") (pintype "power_in"))
      (node (ref "J4") (pin "A1_B12") (pinfunction "GND_A1_B12") (pintype "power_in"))
      (node (ref "J4") (pin "SH1") (pinfunction "SHIELD_SH1") (pintype "passive"))
      (node (ref "J4") (pin "SH2") (pinfunction "SHIELD_SH2") (pintype "passive"))
      (node (ref "J4") (pin "SH3") (pinfunction "SHIELD_SH3") (pintype "passive"))
      (node (ref "J4") (pin "SH4") (pinfunction "SHIELD_SH4") (pintype "passive"))
      (node (ref "R1_USB") (pin "1") (pinfunction "1_1") (pintype "bidirectional"))
      (node (ref "R2_EP_DR") (pin "1") (pinfunction "1_1") (pintype "bidirectional"))
      (node (ref "R2_USB") (pin "2") (pinfunction "2_2") (pintype "bidirectional"))
      (node (ref "R3") (pin "1") (pinfunction "1_1") (pintype "bidirectional"))
      (node (ref "R9") (pin "1") (pinfunction "1_1") (pintype "bidirectional"))
      (node (ref "R_TYPE_SEL") (pin "1") (pinfunction "1_1") (pintype "bidirectional"))
      (node (ref "SJ1") (pin "1") (pinfunction "1_1") (pintype "passive"))
      (node (ref "SW_DN") (pin "1") (pinfunction "1_1") (pintype "passive"))
      (node (ref "SW_ENT") (pin "1") (pinfunction "1_1") (pintype "passive"))
      (node (ref "SW_UP") (pin "1") (pinfunction "1_1") (pintype "passive"))
      (node (ref "TP_BAT_GND") (pin "TP") (pinfunction "TP_TP") (pintype "input"))
      (node (ref "TP_GND") (pin "TP") (pinfunction "TP_TP") (pintype "input"))
      (node (ref "U1") (pin "P$74") (pinfunction "VSS_PAD_P$74") (pintype "bidirectional"))
      (node (ref "U1") (pin "P$75") (pinfunction "VSS_PAD_P$75") (pintype "bidirectional"))
      (node (ref "U1") (pin "P$76") (pinfunction "VSS_PAD_P$76") (pintype "bidirectional"))
      (node (ref "U1") (pin "P$77") (pinfunction "VSS_PAD_P$77") (pintype "bidirectional"))
      (node (ref "U1") (pin "P$78") (pinfunction "VSS_PAD_P$78") (pintype "bidirectional"))
      (node (ref "U1") (pin "P$79") (pinfunction "VSS_PAD_P$79") (pintype "bidirectional"))
      (node (ref "U1") (pin "P$80") (pinfunction "VSS_PAD_P$80") (pintype "bidirectional"))
      (node (ref "U1") (pin "P$81") (pinfunction "VSS_PAD_P$81") (pintype "bidirectional"))
      (node (ref "U1") (pin "P$82") (pinfunction "VSS_PAD_P$82") (pintype "bidirectional"))
      (node (ref "U1") (pin "P$83") (pinfunction "VSS_PAD_P$83") (pintype "bidirectional"))
      (node (ref "U1") (pin "P$84") (pinfunction "VSS_PAD_P$84") (pintype "bidirectional"))
      (node (ref "U1") (pin "P$85") (pinfunction "VSS_PAD_P$85") (pintype "bidirectional"))
      (node (ref "U1") (pin "P$86") (pinfunction "VSS_PAD_P$86") (pintype "bidirectional"))
      (node (ref "U1") (pin "P$87") (pinfunction "VSS_PAD_P$87") (pintype "bidirectional"))
      (node (ref "U1") (pin "P$88") (pinfunction "VSS_PAD_P$88") (pintype "bidirectional"))
      (node (ref "U1") (pin "P$89") (pinfunction "VSS_PAD_P$89") (pintype "bidirectional"))
      (node (ref "U1") (pin "P$90") (pinfunction "VSS_PAD_P$90") (pintype "bidirectional"))
      (node (ref "U1") (pin "P$B7") (pinfunction "VSS_P$B7") (pintype "power_in"))
      (node (ref "U1") (pin "P$F23") (pinfunction "VSS_PA_P$F23") (pintype "bidirectional"))
      (node (ref "U3") (pin "1") (pinfunction "CTG_1") (pintype "power_in"))
      (node (ref "U3") (pin "4") (pinfunction "GND_4") (pintype "power_in"))
      (node (ref "U3") (pin "6") (pinfunction "QSTRT_6") (pintype "input"))
      (node (ref "U3") (pin "9") (pinfunction "EP_9") (pintype "power_in"))
      (node (ref "X1") (pin "2") (pinfunction "2_2") (pintype "passive"))
      (node (ref "X1") (pin "4") (pinfunction "4_4") (pintype "passive"))
    )
    (net (code "24") (name "HAPTIC_EN{slash}1.4C") (class "Default")
      (node (ref "IC2") (pin "A1") (pinfunction "EN_A1") (pintype "bidirectional"))
    )
    (net (code "25") (name "HAPTIC_EN{slash}2.6A") (class "Default")
      (node (ref "U1") (pin "P$U1") (pinfunction "P0.12_P$U1") (pintype "bidirectional"))
    )
    (net (code "26") (name "IMU_INT1") (class "Default")
      (node (ref "IC3") (pin "5") (pinfunction "INT1_5") (pintype "bidirectional"))
      (node (ref "U1") (pin "P$N1") (pinfunction "P0.08_P$N1") (pintype "bidirectional"))
    )
    (net (code "27") (name "IMU_INT2") (class "Default")
      (node (ref "IC3") (pin "6") (pinfunction "INT2_6") (pintype "bidirectional"))
      (node (ref "U1") (pin "P$P2") (pinfunction "P1.08_P$P2") (pintype "bidirectional"))
    )
    (net (code "28") (name "LX1") (class "Default")
      (node (ref "IC9") (pin "B2") (pinfunction "SW1_1_B2") (pintype "bidirectional"))
      (node (ref "IC9") (pin "B3") (pinfunction "SW1_2_B3") (pintype "bidirectional"))
      (node (ref "L7") (pin "1") (pinfunction "1_1") (pintype "bidirectional"))
    )
    (net (code "29") (name "LX2") (class "Default")
      (node (ref "IC9") (pin "D2") (pinfunction "SW2_1_D2") (pintype "bidirectional"))
      (node (ref "IC9") (pin "D3") (pinfunction "SW2_2_D3") (pintype "bidirectional"))
      (node (ref "L7") (pin "2") (pinfunction "2_2") (pintype "bidirectional"))
    )
    (net (code "30") (name "MOSI{slash}1.5B") (class "Default")
      (node (ref "J1") (pin "14") (pinfunction "14_14") (pintype "bidirectional"))
    )
    (net (code "31") (name "MOSI{slash}2.2D") (class "Default")
      (node (ref "U1") (pin "P$B13") (pinfunction "P0.03/AIN1_P$B13") (pintype "bidirectional"))
    )
    (net (code "32") (name "Net-(D2-K)") (class "Default")
      (node (ref "C2-EP-DR") (pin "1") (pinfunction "1_1") (pintype "passive"))
      (node (ref "D2") (pin "1") (pinfunction "K_1") (pintype "bidirectional"))
      (node (ref "D4") (pin "2") (pinfunction "A_2") (pintype "bidirectional"))
    )
    (net (code "33") (name "Net-(D5-A)") (class "Default")
      (node (ref "C2-EP-DR") (pin "2") (pinfunction "2_2") (pintype "passive"))
      (node (ref "D5") (pin "2") (pinfunction "A_2") (pintype "bidirectional"))
      (node (ref "L5") (pin "2") (pinfunction "2_2") (pintype "passive"))
      (node (ref "Q3") (pin "3") (pinfunction "D_3") (pintype "bidirectional"))
    )
    (net (code "34") (name "Net-(EPD_C1-Pad2)") (class "Default")
      (node (ref "EPD_C1") (pin "2") (pinfunction "2_2") (pintype "passive"))
      (node (ref "J1") (pin "5") (pinfunction "5_5") (pintype "bidirectional"))
    )
    (net (code "35") (name "Net-(EPD_C2-Pad2)") (class "Default")
      (node (ref "EPD_C2") (pin "2") (pinfunction "2_2") (pintype "passive"))
      (node (ref "J1") (pin "4") (pinfunction "4_4") (pintype "bidirectional"))
    )
    (net (code "36") (name "Net-(EPD_C6-Pad2)") (class "Default")
      (node (ref "EPD_C6") (pin "2") (pinfunction "2_2") (pintype "passive"))
      (node (ref "J1") (pin "18") (pinfunction "18_18") (pintype "bidirectional"))
    )
    (net (code "37") (name "Net-(EPD_C7-Pad2)") (class "Default")
      (node (ref "EPD_C7") (pin "2") (pinfunction "2_2") (pintype "passive"))
      (node (ref "J1") (pin "19") (pinfunction "19_19") (pintype "bidirectional"))
    )
    (net (code "38") (name "Net-(EPD_C8-Pad2)") (class "Default")
      (node (ref "EPD_C8") (pin "2") (pinfunction "2_2") (pintype "passive"))
      (node (ref "J1") (pin "20") (pinfunction "20_20") (pintype "bidirectional"))
    )
    (net (code "39") (name "Net-(EPD_C10-Pad2)") (class "Default")
      (node (ref "EPD_C10") (pin "2") (pinfunction "2_2") (pintype "passive"))
      (node (ref "J1") (pin "22") (pinfunction "22_22") (pintype "bidirectional"))
    )
    (net (code "40") (name "Net-(EPD_C12-Pad2)") (class "Default")
      (node (ref "EPD_C12") (pin "2") (pinfunction "2_2") (pintype "passive"))
      (node (ref "J1") (pin "24") (pinfunction "24_24") (pintype "bidirectional"))
    )
    (net (code "41") (name "Net-(IC1-TS{slash}MR)") (class "Default")
      (node (ref "IC1") (pin "D1") (pinfunction "TS/MR_D1") (pintype "bidirectional"))
      (node (ref "R9") (pin "2") (pinfunction "2_2") (pintype "bidirectional"))
    )
    (net (code "42") (name "Net-(IC2-REG)") (class "Default")
      (node (ref "C32") (pin "2") (pinfunction "2_2") (pintype "passive"))
      (node (ref "IC2") (pin "A2") (pinfunction "REG_A2") (pintype "bidirectional"))
    )
    (net (code "43") (name "Net-(IC3-SDO)") (class "Default")
      (node (ref "IC3") (pin "1") (pinfunction "SDO_1") (pintype "bidirectional"))
      (node (ref "R3") (pin "2") (pinfunction "2_2") (pintype "bidirectional"))
    )
    (net (code "44") (name "Net-(IC9-SCL)") (class "Default")
      (node (ref "IC9") (pin "D1") (pinfunction "SCL_D1") (pintype "bidirectional"))
      (node (ref "R4") (pin "2") (pinfunction "2_2") (pintype "bidirectional"))
    )
    (net (code "45") (name "Net-(IC9-SDA)") (class "Default")
      (node (ref "IC9") (pin "E1") (pinfunction "SDA_E1") (pintype "bidirectional"))
      (node (ref "R2") (pin "2") (pinfunction "2_2") (pintype "bidirectional"))
    )
    (net (code "46") (name "Net-(J4-CC1)") (class "Default")
      (node (ref "J4") (pin "A5") (pinfunction "CC1_A5") (pintype "bidirectional"))
      (node (ref "R1_USB") (pin "2") (pinfunction "2_2") (pintype "bidirectional"))
    )
    (net (code "47") (name "Net-(J4-CC2)") (class "Default")
      (node (ref "J4") (pin "B5") (pinfunction "CC2_B5") (pintype "bidirectional"))
      (node (ref "R2_USB") (pin "1") (pinfunction "1_1") (pintype "bidirectional"))
    )
    (net (code "48") (name "Net-(L2-Pad2)") (class "Default")
      (node (ref "L2") (pin "2") (pinfunction "2_2") (pintype "passive"))
      (node (ref "L3") (pin "1") (pinfunction "1_1") (pintype "passive"))
    )
    (net (code "49") (name "Net-(R1_EP_DR-Pad1)") (class "Default")
      (node (ref "R1_EP_DR") (pin "1") (pinfunction "1_1") (pintype "bidirectional"))
      (node (ref "R_TYPE_SEL") (pin "2") (pinfunction "2_2") (pintype "bidirectional"))
      (node (ref "SJ1") (pin "2") (pinfunction "2_2") (pintype "passive"))
    )
    (net (code "50") (name "Net-(U1-ANT)") (class "Default")
      (node (ref "C3") (pin "1") (pinfunction "1_1") (pintype "passive"))
      (node (ref "L1") (pin "1") (pinfunction "1_1") (pintype "passive"))
      (node (ref "U1") (pin "P$H23") (pinfunction "ANT_P$H23") (pintype "bidirectional"))
    )
    (net (code "51") (name "Net-(U1-DCC)") (class "Default")
      (node (ref "L2") (pin "1") (pinfunction "1_1") (pintype "passive"))
      (node (ref "U1") (pin "P$B3") (pinfunction "DCC_P$B3") (pintype "output"))
    )
    (net (code "52") (name "Net-(U1-DEC1)") (class "Default")
      (node (ref "C5") (pin "1") (pinfunction "1_1") (pintype "passive"))
      (node (ref "U1") (pin "P$C1") (pinfunction "DEC1_P$C1") (pintype "power_in"))
    )
    (net (code "53") (name "Net-(U1-DEC2)") (class "Default")
      (node (ref "C13") (pin "1") (pinfunction "1_1") (pintype "passive"))
      (node (ref "U1") (pin "P$A18") (pinfunction "DEC2_P$A18") (pintype "bidirectional"))
    )
    (net (code "54") (name "Net-(U1-DEC3V3)") (class "Default")
      (node (ref "C20") (pin "1") (pinfunction "1_1") (pintype "passive"))
      (node (ref "U1") (pin "P$AC5") (pinfunction "DEC3V3_P$AC5") (pintype "bidirectional"))
    )
    (net (code "55") (name "Net-(U1-DEC5)") (class "Default")
      (node (ref "C9") (pin "1") (pinfunction "1_1") (pintype "passive"))
      (node (ref "U1") (pin "P$N24") (pinfunction "DEC5_P$N24") (pintype "bidirectional"))
    )
    (net (code "56") (name "Net-(U1-XC1)") (class "Default")
      (node (ref "C1") (pin "1") (pinfunction "1_1") (pintype "passive"))
      (node (ref "U1") (pin "P$B24") (pinfunction "XC1_P$B24") (pintype "input"))
      (node (ref "X1") (pin "1") (pinfunction "1_1") (pintype "passive"))
    )
    (net (code "57") (name "Net-(U1-XC2)") (class "Default")
      (node (ref "C2") (pin "1") (pinfunction "1_1") (pintype "passive"))
      (node (ref "U1") (pin "P$A23") (pinfunction "XC2_P$A23") (pintype "output"))
      (node (ref "X1") (pin "3") (pinfunction "3_3") (pintype "passive"))
    )
    (net (code "58") (name "OUT+") (class "Default")
      (node (ref "IC2") (pin "A3") (pinfunction "OUT+_A3") (pintype "bidirectional"))
      (node (ref "TP_OP") (pin "TP") (pinfunction "TP_TP") (pintype "input"))
    )
    (net (code "59") (name "OUT-") (class "Default")
      (node (ref "IC2") (pin "C3") (pinfunction "OUT-_C3") (pintype "bidirectional"))
      (node (ref "TP_ON") (pin "TP") (pinfunction "TP_TP") (pintype "input"))
    )
    (net (code "60") (name "P0.00{slash}XL1") (class "Default")
      (node (ref "C17") (pin "2") (pinfunction "2_2") (pintype "passive"))
      (node (ref "U1") (pin "P$D2") (pinfunction "P0.00/XL1_P$D2") (pintype "bidirectional"))
      (node (ref "X2") (pin "1") (pinfunction "1_1") (pintype "passive"))
    )
    (net (code "61") (name "P0.01{slash}XL2") (class "Default")
      (node (ref "C18") (pin "2") (pinfunction "2_2") (pintype "passive"))
      (node (ref "U1") (pin "P$F2") (pinfunction "P0.01/XL2_P$F2") (pintype "bidirectional"))
      (node (ref "X2") (pin "2") (pinfunction "2_2") (pintype "passive"))
    )
    (net (code "62") (name "P0.04") (class "Default")
      (node (ref "U1") (pin "P$J1") (pinfunction "P0.04/AIN2_P$J1") (pintype "bidirectional"))
    )
    (net (code "63") (name "P0.09") (class "Default")
      (node (ref "U1") (pin "P$L24") (pinfunction "P0.09/NFC1_P$L24") (pintype "bidirectional"))
    )
    (net (code "64") (name "P0.13{slash}1.5D") (class "Default")
      (node (ref "C30") (pin "2") (pinfunction "2_2") (pintype "passive"))
      (node (ref "R5") (pin "1") (pinfunction "1_1") (pintype "bidirectional"))
      (node (ref "SW_UP") (pin "2") (pinfunction "2_2") (pintype "passive"))
    )
    (net (code "65") (name "P0.13{slash}2.6C") (class "Default")
      (node (ref "U1") (pin "P$AD8") (pinfunction "P0.13_P$AD8") (pintype "bidirectional"))
    )
    (net (code "66") (name "P0.14{slash}1.5D") (class "Default")
      (node (ref "C31") (pin "2") (pinfunction "2_2") (pintype "passive"))
      (node (ref "R8") (pin "1") (pinfunction "1_1") (pintype "bidirectional"))
      (node (ref "SW_ENT") (pin "2") (pinfunction "2_2") (pintype "passive"))
    )
    (net (code "67") (name "P0.14{slash}2,7C") (class "Default")
      (node (ref "U1") (pin "P$AC9") (pinfunction "P0.14_P$AC9") (pintype "bidirectional"))
    )
    (net (code "68") (name "P0.19") (class "Default")
      (node (ref "U1") (pin "P$AC15") (pinfunction "P0.19_P$AC15") (pintype "bidirectional"))
    )
    (net (code "69") (name "P0.20") (class "Default")
      (node (ref "U1") (pin "P$AD16") (pinfunction "P0.20_P$AD16") (pintype "bidirectional"))
    )
    (net (code "70") (name "P0.21") (class "Default")
      (node (ref "U1") (pin "P$AC17") (pinfunction "P0.21_P$AC17") (pintype "bidirectional"))
    )
    (net (code "71") (name "P0.22") (class "Default")
      (node (ref "U1") (pin "P$AD18") (pinfunction "P0.22_P$AD18") (pintype "bidirectional"))
    )
    (net (code "72") (name "P0.23") (class "Default")
      (node (ref "U1") (pin "P$AC19") (pinfunction "P0.23_P$AC19") (pintype "bidirectional"))
    )
    (net (code "73") (name "P0.24") (class "Default")
      (node (ref "U1") (pin "P$AD20") (pinfunction "P0.24_P$AD20") (pintype "bidirectional"))
    )
    (net (code "74") (name "P0.25") (class "Default")
      (node (ref "U1") (pin "P$AC21") (pinfunction "P0.25_P$AC21") (pintype "bidirectional"))
    )
    (net (code "75") (name "P0.26") (class "Default")
      (node (ref "U1") (pin "P$G1") (pinfunction "P0.26_P$G1") (pintype "bidirectional"))
    )
    (net (code "76") (name "P0.27") (class "Default")
      (node (ref "U1") (pin "P$H2") (pinfunction "P0.27_P$H2") (pintype "bidirectional"))
    )
    (net (code "77") (name "P0.28") (class "Default")
      (node (ref "U1") (pin "P$B11") (pinfunction "P0.28/AIN4_P$B11") (pintype "bidirectional"))
    )
    (net (code "78") (name "P0.29") (class "Default")
      (node (ref "U1") (pin "P$A10") (pinfunction "P0.29/AIN5_P$A10") (pintype "bidirectional"))
    )
    (net (code "79") (name "P0.30") (class "Default")
      (node (ref "U1") (pin "P$B9") (pinfunction "P0.30/AIN6_P$B9") (pintype "bidirectional"))
    )
    (net (code "80") (name "P0.31") (class "Default")
      (node (ref "U1") (pin "P$A8") (pinfunction "P0.31/AIN7_P$A8") (pintype "bidirectional"))
    )
    (net (code "81") (name "P1.01{slash}1.6C") (class "Default")
      (node (ref "Q1") (pin "1") (pinfunction "G_1") (pintype "bidirectional"))
      (node (ref "R_PWR_EPD") (pin "1") (pinfunction "1_1") (pintype "bidirectional"))
    )
    (net (code "82") (name "P1.01{slash}2.4B") (class "Default")
      (node (ref "U1") (pin "P$Y23") (pinfunction "P1.01_P$Y23") (pintype "bidirectional"))
    )
    (net (code "83") (name "P1.02{slash}1.6C") (class "Default")
      (node (ref "C29") (pin "2") (pinfunction "2_2") (pintype "passive"))
      (node (ref "R7") (pin "1") (pinfunction "1_1") (pintype "bidirectional"))
      (node (ref "SW_DN") (pin "2") (pinfunction "2_2") (pintype "passive"))
    )
    (net (code "84") (name "P1.02{slash}2.8C") (class "Default")
      (node (ref "U1") (pin "P$W24") (pinfunction "P1.02_P$W24") (pintype "bidirectional"))
    )
    (net (code "85") (name "P1.03") (class "Default")
      (node (ref "U1") (pin "P$V23") (pinfunction "P1.03_P$V23") (pintype "bidirectional"))
    )
    (net (code "86") (name "P1.04") (class "Default")
      (node (ref "U1") (pin "P$U24") (pinfunction "P1.04_P$U24") (pintype "bidirectional"))
    )
    (net (code "87") (name "P1.05") (class "Default")
      (node (ref "U1") (pin "P$T23") (pinfunction "P1.05_P$T23") (pintype "bidirectional"))
    )
    (net (code "88") (name "P1.06") (class "Default")
      (node (ref "U1") (pin "P$R24") (pinfunction "P1.06_P$R24") (pintype "bidirectional"))
    )
    (net (code "89") (name "P1.07") (class "Default")
      (node (ref "U1") (pin "P$P23") (pinfunction "P1.07_P$P23") (pintype "bidirectional"))
    )
    (net (code "90") (name "P1.09") (class "Default")
      (node (ref "U1") (pin "P$R1") (pinfunction "P1.09_P$R1") (pintype "bidirectional"))
    )
    (net (code "91") (name "P1.10") (class "Default")
      (node (ref "U1") (pin "P$A20") (pinfunction "P1.10_P$A20") (pintype "bidirectional"))
    )
    (net (code "92") (name "P1.11") (class "Default")
      (node (ref "U1") (pin "P$B19") (pinfunction "P1.11_P$B19") (pintype "bidirectional"))
    )
    (net (code "93") (name "P1.12") (class "Default")
      (node (ref "U1") (pin "P$B17") (pinfunction "P1.12_P$B17") (pintype "bidirectional"))
    )
    (net (code "94") (name "P1.13") (class "Default")
      (node (ref "U1") (pin "P$A16") (pinfunction "P1.13_P$A16") (pintype "bidirectional"))
    )
    (net (code "95") (name "P1.14") (class "Default")
      (node (ref "U1") (pin "P$B15") (pinfunction "P1.14_P$B15") (pintype "bidirectional"))
    )
    (net (code "96") (name "P1.15") (class "Default")
      (node (ref "U1") (pin "P$A14") (pinfunction "P1.15_P$A14") (pintype "bidirectional"))
    )
    (net (code "97") (name "PMIC_INT") (class "Default")
      (node (ref "IC1") (pin "A1") (pinfunction "~{INT}_A1") (pintype "bidirectional"))
      (node (ref "U1") (pin "P$T2") (pinfunction "P0.11_P$T2") (pintype "bidirectional"))
    )
    (net (code "98") (name "PREVGH") (class "Default")
      (node (ref "D5") (pin "1") (pinfunction "K_1") (pintype "bidirectional"))
      (node (ref "EPD_C9") (pin "2") (pinfunction "2_2") (pintype "passive"))
      (node (ref "J1") (pin "21") (pinfunction "21_21") (pintype "bidirectional"))
    )
    (net (code "99") (name "PREVGL") (class "Default")
      (node (ref "D2") (pin "2") (pinfunction "A_2") (pintype "bidirectional"))
      (node (ref "EPD_C11") (pin "2") (pinfunction "2_2") (pintype "passive"))
      (node (ref "J1") (pin "23") (pinfunction "23_23") (pintype "bidirectional"))
    )
    (net (code "100") (name "RESE") (class "Default")
      (node (ref "J1") (pin "3") (pinfunction "3_3") (pintype "bidirectional"))
      (node (ref "Q3") (pin "2") (pinfunction "S_2") (pintype "bidirectional"))
      (node (ref "R1_EP_DR") (pin "2") (pinfunction "2_2") (pintype "bidirectional"))
    )
    (net (code "101") (name "RESET") (class "Default")
      (node (ref "J2") (pin "6") (pinfunction "6_6") (pintype "bidirectional"))
      (node (ref "TP_RESET") (pin "TP") (pinfunction "TP_TP") (pintype "input"))
      (node (ref "U1") (pin "P$AC13") (pinfunction "P0.18/RESET_P$AC13") (pintype "bidirectional"))
    )
    (net (code "102") (name "RF") (class "Default")
      (node (ref "ANT1") (pin "1") (pinfunction "FEED_1") (pintype "input"))
      (node (ref "C22") (pin "1") (pinfunction "1_1") (pintype "passive"))
      (node (ref "C4") (pin "1") (pinfunction "1_1") (pintype "passive"))
      (node (ref "L1") (pin "2") (pinfunction "2_2") (pintype "passive"))
    )
    (net (code "103") (name "SCK{slash}1.5B") (class "Default")
      (node (ref "J1") (pin "13") (pinfunction "13_13") (pintype "bidirectional"))
    )
    (net (code "104") (name "SCK{slash}2.2D") (class "Default")
      (node (ref "U1") (pin "P$A12") (pinfunction "P0.02/AIN0_P$A12") (pintype "bidirectional"))
    )
    (net (code "105") (name "SCL{slash}1.4C") (class "Default")
      (node (ref "IC2") (pin "C1") (pinfunction "SCL_C1") (pintype "bidirectional"))
      (node (ref "U3") (pin "7") (pinfunction "SCL_7") (pintype "input"))
    )
    (net (code "106") (name "SCL{slash}2.4C") (class "Default")
      (node (ref "IC1") (pin "B1") (pinfunction "SCL_B1") (pintype "bidirectional"))
      (node (ref "IC3") (pin "12") (pinfunction "SCX_12") (pintype "bidirectional"))
      (node (ref "R17") (pin "2") (pinfunction "2_2") (pintype "bidirectional"))
      (node (ref "R4") (pin "1") (pinfunction "1_1") (pintype "bidirectional"))
      (node (ref "TP_SCL") (pin "TP") (pinfunction "TP_TP") (pintype "input"))
      (node (ref "U1") (pin "P$M2") (pinfunction "P0.07_P$M2") (pintype "bidirectional"))
    )
    (net (code "107") (name "SDA{slash}1.4C") (class "Default")
      (node (ref "IC2") (pin "B2") (pinfunction "SDA_B2") (pintype "bidirectional"))
      (node (ref "U3") (pin "8") (pinfunction "SDA_8") (pintype "bidirectional"))
    )
    (net (code "108") (name "SDA{slash}2.4C") (class "Default")
      (node (ref "IC1") (pin "C1") (pinfunction "SDA_C1") (pintype "bidirectional"))
      (node (ref "IC3") (pin "2") (pinfunction "SDX_2") (pintype "bidirectional"))
      (node (ref "R18") (pin "2") (pinfunction "2_2") (pintype "bidirectional"))
      (node (ref "R2") (pin "1") (pinfunction "1_1") (pintype "bidirectional"))
      (node (ref "TP_SDA") (pin "TP") (pinfunction "TP_TP") (pintype "input"))
      (node (ref "U1") (pin "P$L1") (pinfunction "P0.06_P$L1") (pintype "bidirectional"))
    )
    (net (code "109") (name "SWDCLK") (class "Default")
      (node (ref "J2") (pin "4") (pinfunction "4_4") (pintype "bidirectional"))
      (node (ref "TP_SWDCLK") (pin "TP") (pinfunction "TP_TP") (pintype "input"))
      (node (ref "U1") (pin "P$AA24") (pinfunction "SWDCLK_P$AA24") (pintype "input"))
    )
    (net (code "110") (name "SWDIO") (class "Default")
      (node (ref "J2") (pin "2") (pinfunction "2_2") (pintype "bidirectional"))
      (node (ref "TP_SWDIO") (pin "TP") (pinfunction "TP_TP") (pintype "input"))
      (node (ref "U1") (pin "P$AC24") (pinfunction "SWDIO_P$AC24") (pintype "bidirectional"))
    )
    (net (code "111") (name "SWO") (class "Default")
      (node (ref "TP_SWO") (pin "TP") (pinfunction "TP_TP") (pintype "input"))
      (node (ref "U1") (pin "P$AD22") (pinfunction "P1.00_P$AD22") (pintype "bidirectional"))
    )
    (net (code "112") (name "VBAT{slash}1.2A") (class "Default")
      (node (ref "C26") (pin "2") (pinfunction "2_2") (pintype "passive"))
      (node (ref "TP_VBAT") (pin "TP") (pinfunction "TP_TP") (pintype "input"))
      (node (ref "U3") (pin "2") (pinfunction "CELL_2") (pintype "power_in"))
      (node (ref "U3") (pin "3") (pinfunction "VDD_3") (pintype "power_in"))
    )
    (net (code "113") (name "VBAT{slash}2.5C") (class "Default")
      (node (ref "C37") (pin "1") (pinfunction "1_1") (pintype "passive"))
      (node (ref "IC1") (pin "C2") (pinfunction "BAT_C2") (pintype "bidirectional"))
    )
    (net (code "114") (name "VBUS{slash}1.5D") (class "Default")
      (node (ref "C42") (pin "1") (pinfunction "1_1") (pintype "passive"))
      (node (ref "C43") (pin "1") (pinfunction "1_1") (pintype "passive"))
      (node (ref "D3") (pin "5") (pinfunction "VBUS_5") (pintype "bidirectional"))
      (node (ref "J4") (pin "A4_B9") (pinfunction "VBUS_A4_B9") (pintype "power_in"))
      (node (ref "J4") (pin "A9_B4") (pinfunction "VBUS_A9_B4") (pintype "power_in"))
    )
    (net (code "115") (name "VBUS{slash}2.6D") (class "Default")
      (node (ref "C21") (pin "1") (pinfunction "1_1") (pintype "passive"))
      (node (ref "C38") (pin "1") (pinfunction "1_1") (pintype "passive"))
      (node (ref "IC1") (pin "A2") (pinfunction "IN_A2") (pintype "bidirectional"))
      (node (ref "U1") (pin "P$AD2") (pinfunction "VBUS_P$AD2") (pintype "power_in"))
    )
    (net (code "116") (name "VREG") (class "Default")
      (node (ref "C23") (pin "2") (pinfunction "2_2") (pintype "passive"))
      (node (ref "C24") (pin "2") (pinfunction "2_2") (pintype "passive"))
      (node (ref "C39") (pin "1") (pinfunction "1_1") (pintype "passive"))
      (node (ref "IC1") (pin "B2") (pinfunction "SYS_B2") (pintype "bidirectional"))
      (node (ref "IC9") (pin "A1") (pinfunction "EN_A1") (pintype "bidirectional"))
      (node (ref "IC9") (pin "A2") (pinfunction "VIN_1_A2") (pintype "bidirectional"))
      (node (ref "IC9") (pin "A3") (pinfunction "VIN_2_A3") (pintype "bidirectional"))
      (node (ref "TP_VREG") (pin "TP") (pinfunction "TP_TP") (pintype "input"))
    )
    (net (code "117") (name "unconnected-(ANT1-NC-Pad2)") (class "Default")
      (node (ref "ANT1") (pin "2") (pinfunction "NC_2") (pintype "no_connect"))
    )
    (net (code "118") (name "unconnected-(IC3-ASCL-Pad11)") (class "Default")
      (node (ref "IC3") (pin "11") (pinfunction "ASCL_11") (pintype "bidirectional"))
    )
    (net (code "119") (name "unconnected-(IC3-ASDA-Pad4)") (class "Default")
      (node (ref "IC3") (pin "4") (pinfunction "ASDA_4") (pintype "bidirectional"))
    )
    (net (code "120") (name "unconnected-(J1-Pad1)") (class "Default")
      (node (ref "J1") (pin "1") (pinfunction "1_1") (pintype "bidirectional"))
    )
    (net (code "121") (name "unconnected-(J1-Pad6)") (class "Default")
      (node (ref "J1") (pin "6") (pinfunction "6_6") (pintype "bidirectional"))
    )
    (net (code "122") (name "unconnected-(J1-Pad7)") (class "Default")
      (node (ref "J1") (pin "7") (pinfunction "7_7") (pintype "bidirectional"))
    )
    (net (code "123") (name "unconnected-(J4-SBU1-PadA8)") (class "Default")
      (node (ref "J4") (pin "A8") (pinfunction "SBU1_A8") (pintype "bidirectional"))
    )
    (net (code "124") (name "unconnected-(J4-SBU2-PadB8)") (class "Default")
      (node (ref "J4") (pin "B8") (pinfunction "SBU2_B8") (pintype "bidirectional"))
    )
    (net (code "125") (name "unconnected-(U1-DCCH-PadP$AB2)") (class "Default")
      (node (ref "U1") (pin "P$AB2") (pinfunction "DCCH_P$AB2") (pintype "bidirectional"))
    )
  )
)
